# CAN.net
KiCad netlist of a schematic drawn in Altium Designer
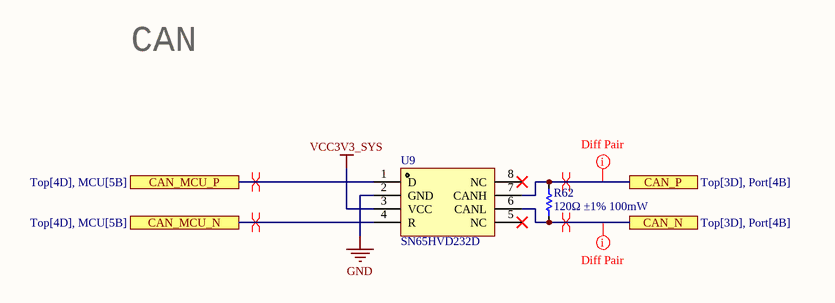
[diagram p0: CAN.SchDoc]

(export (version "E")
  (design (tool "Eeschema 10.0.6"))
  (components
    (comp (ref "R62")
      (value "120Ω ±1% 100mW")
      (footprint "R0603")
      (description "Resistor")
      (fields (field (name "PUBLISHER") "Altium Limited"))
      (libsource (lib "Component") (part "Res"))
    )
    (comp (ref "U9")
      (value "SN65HVD232D")
      (footprint "SOIC127P600X175-8N")
      (fields (field (name "MANUFACTURER") "Texas Instruments"))
      (libsource (lib "IC") (part "SN65HVD232D"))
    )
  )
  (nets
    (net (code "1") (name "/CAN_MCU_N") (class "Default")
      (node (ref "U9") (pin "4") (pinfunction "R_4") (pintype "passive"))
    )
    (net (code "2") (name "/CAN_MCU_P") (class "Default")
      (node (ref "U9") (pin "1") (pinfunction "D_1") (pintype "passive"))
    )
    (net (code "3") (name "/CAN_N") (class "Default")
      (node (ref "R62") (pin "1") (pinfunction "1_1") (pintype "passive"))
      (node (ref "U9") (pin "6") (pinfunction "CANL_6") (pintype "passive"))
    )
    (net (code "4") (name "/CAN_P") (class "Default")
      (node (ref "R62") (pin "2") (pinfunction "2_2") (pintype "passive"))
      (node (ref "U9") (pin "7") (pinfunction "CANH_7") (pintype "passive"))
    )
    (net (code "5") (name "GND") (class "Default")
      (node (ref "U9") (pin "2") (pinfunction "GND_2") (pintype "passive"))
    )
    (net (code "6") (name "VCC3V3_SYS") (class "Default")
      (node (ref "U9") (pin "3") (pinfunction "VCC_3") (pintype "passive"))
    )
    (net (code "7") (name "unconnected-(U9-NC-Pad5)") (class "Default")
      (node (ref "U9") (pin "5") (pinfunction "NC_5") (pintype "passive+no_connect"))
    )
    (net (code "8") (name "unconnected-(U9-NC-Pad8)") (class "Default")
      (node (ref "U9") (pin "8") (pinfunction "NC_8") (pintype "passive+no_connect"))
    )
  )
)
